# JACart2.net
KiCad netlist of a schematic drawn in EAGLE
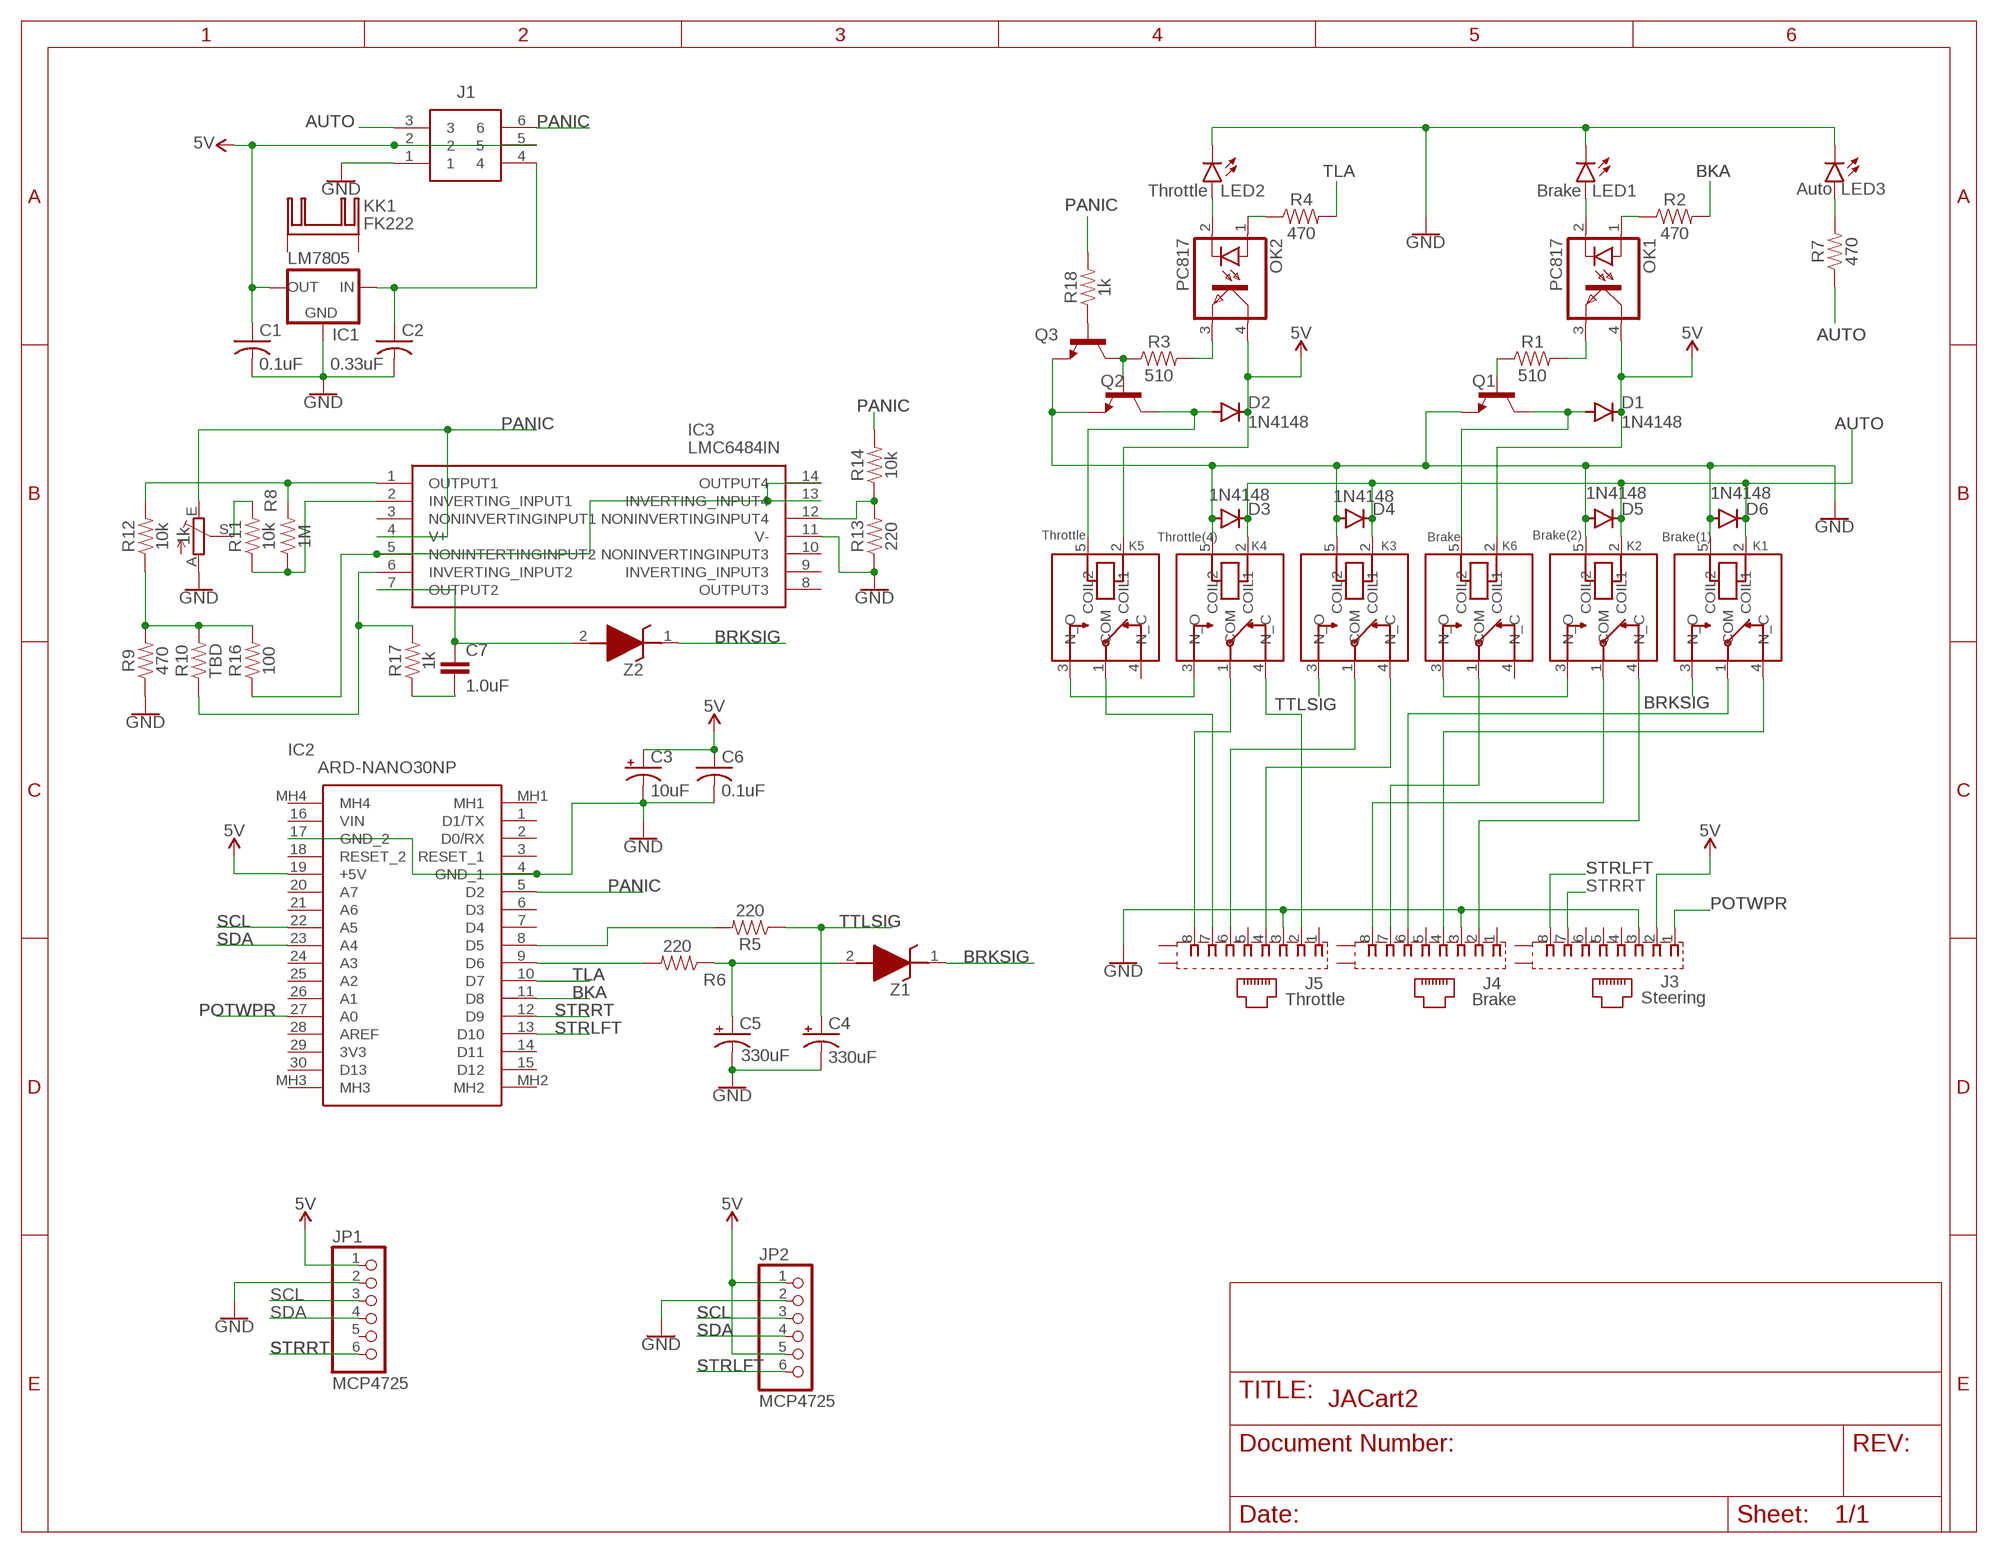
[diagram p0: schematic, sheet 1]

(export (version "E")
  (design (tool "Eeschema 10.0.6"))
  (components
    (comp (ref "C1")
      (value "0.1uF")
      (footprint "eagle-import:C050-024X044")
      (libsource (lib "eagle-import") (part "C-US050-024X044"))
    )
    (comp (ref "C2")
      (value "0.33uF")
      (footprint "eagle-import:C050-024X044")
      (libsource (lib "eagle-import") (part "C-US050-024X044"))
    )
    (comp (ref "C3")
      (value "10uF")
      (footprint "eagle-import:CPOL-RADIAL-2.5MM-5MM")
      (libsource (lib "eagle-import") (part "10UF-POLAR-RADIAL-2.5MM-25V-20%"))
    )
    (comp (ref "C4")
      (value "330uF")
      (footprint "eagle-import:PANASONIC_A")
      (libsource (lib "eagle-import") (part "330UF-PA"))
    )
    (comp (ref "C5")
      (value "330uF")
      (footprint "eagle-import:PANASONIC_A")
      (libsource (lib "eagle-import") (part "330UF-PA"))
    )
    (comp (ref "C6")
      (value "0.1uF")
      (footprint "eagle-import:C050-024X044")
      (fields (field (name "C6") "0.1uF"))
      (libsource (lib "eagle-import") (part "C-US050-024X044"))
    )
    (comp (ref "C7")
      (value "1.0uF")
      (footprint "eagle-import:CAP-PTH-SMALL-KIT")
      (libsource (lib "eagle-import") (part "0.1UF-KIT-EZ-50V-20%"))
    )
    (comp (ref "D1")
      (value "1N4148")
      (footprint "eagle-import:DO35-7")
      (libsource (lib "eagle-import") (part "1N4148DO35-7"))
    )
    (comp (ref "D2")
      (value "1N4148")
      (footprint "eagle-import:DO35-7")
      (libsource (lib "eagle-import") (part "1N4148DO35-7"))
    )
    (comp (ref "D3")
      (value "1N4148")
      (footprint "eagle-import:DO35-7")
      (libsource (lib "eagle-import") (part "1N4148DO35-7"))
    )
    (comp (ref "D4")
      (value "1N4148")
      (footprint "eagle-import:DO35-7")
      (libsource (lib "eagle-import") (part "1N4148DO35-7"))
    )
    (comp (ref "D5")
      (value "1N4148")
      (footprint "eagle-import:DO35-7")
      (libsource (lib "eagle-import") (part "1N4148DO35-7"))
    )
    (comp (ref "D6")
      (value "1N4148")
      (footprint "eagle-import:DO35-7")
      (libsource (lib "eagle-import") (part "1N4148DO35-7"))
    )
    (comp (ref "IC1")
      (value "LM7805")
      (footprint "eagle-import:78XXS")
      (libsource (lib "eagle-import") (part "7805-VR"))
    )
    (comp (ref "IC2")
      (value "ARD-NANO30NP")
      (footprint "eagle-import:ARDNANO30NP")
      (fields (field (name "MOUSER_PART_NUMBER") "992-ARD-NANO30NP"))
      (libsource (lib "eagle-import") (part "ARD-NANO30NP"))
    )
    (comp (ref "IC3")
      (value "LMC6484IN")
      (footprint "eagle-import:DIP794W56P254L1905H533Q14N")
      (fields (field (name "MOUSER_PART_NUMBER") "926-LMC6484IN"))
      (libsource (lib "eagle-import") (part "LMC6484IN"))
    )
    (comp (ref "J1")
      (value "39-30-1060")
      (footprint "eagle-import:39-30-1060_1")
      (fields (field (name "MOUSER_PART_NUMBER") "538-39-30-1060"))
      (libsource (lib "eagle-import") (part "39-30-1060"))
    )
    (comp (ref "J3")
      (value "Steering")
      (footprint "eagle-import:GLX-S-88M")
      (libsource (lib "eagle-import") (part "RJ45-RTANGL"))
    )
    (comp (ref "J4")
      (value "Brake")
      (footprint "eagle-import:GLX-S-88M")
      (fields (field (name "MF") "J4"))
      (libsource (lib "eagle-import") (part "RJ45-RTANGL"))
    )
    (comp (ref "J5")
      (value "Throttle")
      (footprint "eagle-import:GLX-S-88M")
      (libsource (lib "eagle-import") (part "RJ45-RTANGL"))
    )
    (comp (ref "JP1")
      (value "MCP4725")
      (footprint "eagle-import:1X06_ROUND_70")
      (libsource (lib "eagle-import") (part "HEADER-1X670MIL"))
    )
    (comp (ref "JP2")
      (value "MCP4725")
      (footprint "eagle-import:1X06_ROUND_70")
      (libsource (lib "eagle-import") (part "HEADER-1X670MIL"))
    )
    (comp (ref "K1")
      (value "Brake(1)")
      (footprint "eagle-import:RELAY_JS1-5V-F")
      (fields (field (name "MF") "Panasonic Electric") (field (name "MP") "JS1-5V-F"))
      (libsource (lib "eagle-import") (part "RELAY-SPDT"))
    )
    (comp (ref "K2")
      (value "Brake(2)")
      (footprint "eagle-import:RELAY_JS1-5V-F")
      (fields (field (name "MF") "Panasonic Electric") (field (name "MP") "JS1-5V-F"))
      (libsource (lib "eagle-import") (part "RELAY-SPDT"))
    )
    (comp (ref "K3")
      (value "Throttle(3)")
      (footprint "eagle-import:RELAY_JS1-5V-F")
      (fields (field (name "MF") "Panasonic Electric") (field (name "MP") "JS1-5V-F"))
      (libsource (lib "eagle-import") (part "RELAY-SPDT"))
    )
    (comp (ref "K4")
      (value "Throttle(4)")
      (footprint "eagle-import:RELAY_JS1-5V-F")
      (fields (field (name "MF") "Panasonic Electric") (field (name "MP") "JS1-5V-F"))
      (libsource (lib "eagle-import") (part "RELAY-SPDT"))
    )
    (comp (ref "K5")
      (value "Throttle")
      (footprint "eagle-import:RELAY_JS1-5V-F")
      (fields (field (name "MF") "Panasonic Electric") (field (name "MP") "JS1-5V-F"))
      (libsource (lib "eagle-import") (part "RELAY-SPDT"))
    )
    (comp (ref "K6")
      (value "Brake")
      (footprint "eagle-import:RELAY_JS1-5V-F")
      (fields (field (name "MF") "Panasonic Electric") (field (name "MP") "JS1-5V-F"))
      (libsource (lib "eagle-import") (part "RELAY-SPDT"))
    )
    (comp (ref "KK1")
      (value "FK222")
      (footprint "eagle-import:FK222")
      (libsource (lib "eagle-import") (part "FK222"))
    )
    (comp (ref "LED1")
      (value "Brake")
      (footprint "eagle-import:LED_5MM")
      (libsource (lib "eagle-import") (part "LED5MM"))
    )
    (comp (ref "LED2")
      (value "Throttle")
      (footprint "eagle-import:LED_5MM")
      (libsource (lib "eagle-import") (part "LED5MM"))
    )
    (comp (ref "LED3")
      (value "Auto")
      (footprint "eagle-import:LED_5MM")
      (libsource (lib "eagle-import") (part "LED5MM"))
    )
    (comp (ref "OK1")
      (value "PC817")
      (footprint "eagle-import:DIL04")
      (fields (field (name "MPN") "PC817X4J000F"))
      (libsource (lib "eagle-import") (part "PC817"))
    )
    (comp (ref "OK2")
      (value "PC817")
      (footprint "eagle-import:DIL04")
      (fields (field (name "MPN") "PC817X4J000F"))
      (libsource (lib "eagle-import") (part "PC817"))
    )
    (comp (ref "Q1")
      (value "2N3904")
      (footprint "eagle-import:TO92")
      (libsource (lib "eagle-import") (part "2N3904"))
    )
    (comp (ref "Q2")
      (value "2N3904")
      (footprint "eagle-import:TO92")
      (libsource (lib "eagle-import") (part "2N3904"))
    )
    (comp (ref "Q3")
      (value "2N3904")
      (footprint "eagle-import:TO92")
      (libsource (lib "eagle-import") (part "2N3904"))
    )
    (comp (ref "R1")
      (value "510")
      (footprint "eagle-import:AXIAL-0.3")
      (libsource (lib "eagle-import") (part "RESISTORAXIAL-0.3"))
    )
    (comp (ref "R2")
      (value "470")
      (footprint "eagle-import:AXIAL-0.3")
      (libsource (lib "eagle-import") (part "RESISTORAXIAL-0.3"))
    )
    (comp (ref "R3")
      (value "510")
      (footprint "eagle-import:AXIAL-0.3")
      (libsource (lib "eagle-import") (part "RESISTORAXIAL-0.3"))
    )
    (comp (ref "R4")
      (value "470")
      (footprint "eagle-import:AXIAL-0.3")
      (libsource (lib "eagle-import") (part "RESISTORAXIAL-0.3"))
    )
    (comp (ref "R5")
      (value "220")
      (footprint "eagle-import:AXIAL-0.3")
      (libsource (lib "eagle-import") (part "RESISTORAXIAL-0.3"))
    )
    (comp (ref "R6")
      (value "220")
      (footprint "eagle-import:AXIAL-0.3")
      (libsource (lib "eagle-import") (part "RESISTORAXIAL-0.3"))
    )
    (comp (ref "R7")
      (value "470")
      (footprint "eagle-import:AXIAL-0.3")
      (libsource (lib "eagle-import") (part "RESISTORAXIAL-0.3"))
    )
    (comp (ref "R8")
      (value "1M")
      (footprint "eagle-import:AXIAL-0.3")
      (libsource (lib "eagle-import") (part "RESISTORAXIAL-0.3"))
    )
    (comp (ref "R9")
      (value "470")
      (footprint "eagle-import:AXIAL-0.3")
      (libsource (lib "eagle-import") (part "RESISTORAXIAL-0.3"))
    )
    (comp (ref "R10")
      (value "TBD")
      (footprint "eagle-import:AXIAL-0.3")
      (libsource (lib "eagle-import") (part "RESISTORAXIAL-0.3"))
    )
    (comp (ref "R11")
      (value "10k")
      (footprint "eagle-import:AXIAL-0.3")
      (libsource (lib "eagle-import") (part "RESISTORAXIAL-0.3"))
    )
    (comp (ref "R12")
      (value "10k")
      (footprint "eagle-import:AXIAL-0.3")
      (libsource (lib "eagle-import") (part "RESISTORAXIAL-0.3"))
    )
    (comp (ref "R13")
      (value "220")
      (footprint "eagle-import:AXIAL-0.3")
      (libsource (lib "eagle-import") (part "RESISTORAXIAL-0.3"))
    )
    (comp (ref "R14")
      (value "10k")
      (footprint "eagle-import:AXIAL-0.3")
      (libsource (lib "eagle-import") (part "RESISTORAXIAL-0.3"))
    )
    (comp (ref "R15")
      (value "1k")
      (footprint "eagle-import:RJ9W")
      (libsource (lib "eagle-import") (part "TRIM_EU-RJ9W"))
    )
    (comp (ref "R16")
      (value "100")
      (footprint "eagle-import:AXIAL-0.3")
      (libsource (lib "eagle-import") (part "RESISTORAXIAL-0.3"))
    )
    (comp (ref "R17")
      (value "1k")
      (footprint "eagle-import:AXIAL-0.3")
      (libsource (lib "eagle-import") (part "RESISTORAXIAL-0.3"))
    )
    (comp (ref "R18")
      (value "1k")
      (footprint "eagle-import:AXIAL-0.3")
      (libsource (lib "eagle-import") (part "RESISTORAXIAL-0.3"))
    )
    (comp (ref "Z1")
      (value "BAT85S-TR")
      (footprint "eagle-import:DIOAD950W60L350D150")
      (fields (field (name "MOUSER_PART_NUMBER") "78-BAT85S"))
      (libsource (lib "eagle-import") (part "BAT85S-TR"))
    )
    (comp (ref "Z2")
      (value "BAT85S-TR")
      (footprint "eagle-import:DIOAD950W60L350D150")
      (fields (field (name "MOUSER_PART_NUMBER") "78-BAT85S"))
      (libsource (lib "eagle-import") (part "BAT85S-TR"))
    )
  )
  (nets
    (net (code "1") (name "/AUTO") (class "Default")
      (node (ref "D3") (pin "C") (pinfunction "C_C") (pintype "passive"))
      (node (ref "D4") (pin "C") (pinfunction "C_C") (pintype "passive"))
      (node (ref "D5") (pin "C") (pinfunction "C_C") (pintype "passive"))
      (node (ref "D6") (pin "C") (pinfunction "C_C") (pintype "passive"))
      (node (ref "J1") (pin "3") (pinfunction "3_3") (pintype "bidirectional"))
      (node (ref "K1") (pin "2") (pinfunction "COIL1_2") (pintype "passive"))
      (node (ref "K2") (pin "2") (pinfunction "COIL1_2") (pintype "passive"))
      (node (ref "K3") (pin "2") (pinfunction "COIL1_2") (pintype "passive"))
      (node (ref "K4") (pin "2") (pinfunction "COIL1_2") (pintype "passive"))
      (node (ref "R7") (pin "P$1") (pinfunction "1_P$1") (pintype "passive"))
    )
    (net (code "2") (name "/BKA") (class "Default")
      (node (ref "IC2") (pin "11") (pinfunction "D8_11") (pintype "bidirectional"))
      (node (ref "R2") (pin "P$2") (pinfunction "2_P$2") (pintype "passive"))
    )
    (net (code "3") (name "/BRKSIG") (class "Default")
      (node (ref "K1") (pin "3") (pinfunction "N_O_3") (pintype "passive"))
      (node (ref "Z1") (pin "1") (pinfunction "K_1") (pintype "bidirectional"))
      (node (ref "Z2") (pin "1") (pinfunction "K_1") (pintype "bidirectional"))
    )
    (net (code "4") (name "/PANIC") (class "Default")
      (node (ref "IC2") (pin "5") (pinfunction "D2_5") (pintype "bidirectional"))
      (node (ref "IC3") (pin "4") (pinfunction "V+_4") (pintype "bidirectional"))
      (node (ref "J1") (pin "6") (pinfunction "6_6") (pintype "bidirectional"))
      (node (ref "R14") (pin "P$2") (pinfunction "2_P$2") (pintype "passive"))
      (node (ref "R15") (pin "E") (pinfunction "E_E") (pintype "passive"))
      (node (ref "R18") (pin "P$2") (pinfunction "2_P$2") (pintype "passive"))
    )
    (net (code "5") (name "/POTWPR") (class "Default")
      (node (ref "IC2") (pin "27") (pinfunction "A0_27") (pintype "bidirectional"))
      (node (ref "J3") (pin "1") (pinfunction "1_1") (pintype "passive"))
    )
    (net (code "6") (name "/SCL") (class "Default")
      (node (ref "IC2") (pin "22") (pinfunction "A5_22") (pintype "bidirectional"))
      (node (ref "JP1") (pin "3") (pinfunction "3_3") (pintype "passive"))
      (node (ref "JP2") (pin "3") (pinfunction "3_3") (pintype "passive"))
    )
    (net (code "7") (name "/SDA") (class "Default")
      (node (ref "IC2") (pin "23") (pinfunction "A4_23") (pintype "bidirectional"))
      (node (ref "JP1") (pin "4") (pinfunction "4_4") (pintype "passive"))
      (node (ref "JP2") (pin "4") (pinfunction "4_4") (pintype "passive"))
    )
    (net (code "8") (name "/STRLFT") (class "Default")
      (node (ref "IC2") (pin "13") (pinfunction "D10_13") (pintype "bidirectional"))
      (node (ref "J3") (pin "8") (pinfunction "8_8") (pintype "passive"))
      (node (ref "JP2") (pin "6") (pinfunction "6_6") (pintype "passive"))
    )
    (net (code "9") (name "/STRRT") (class "Default")
      (node (ref "IC2") (pin "12") (pinfunction "D9_12") (pintype "bidirectional"))
      (node (ref "J3") (pin "7") (pinfunction "7_7") (pintype "passive"))
      (node (ref "JP1") (pin "6") (pinfunction "6_6") (pintype "passive"))
    )
    (net (code "10") (name "/TLA") (class "Default")
      (node (ref "IC2") (pin "10") (pinfunction "D7_10") (pintype "bidirectional"))
      (node (ref "R4") (pin "P$2") (pinfunction "2_P$2") (pintype "passive"))
    )
    (net (code "11") (name "/TTLSIG") (class "Default")
      (node (ref "C4") (pin "+") (pinfunction "+_+") (pintype "passive"))
      (node (ref "K3") (pin "3") (pinfunction "N_O_3") (pintype "passive"))
      (node (ref "R5") (pin "P$1") (pinfunction "1_P$1") (pintype "passive"))
    )
    (net (code "12") (name "5V") (class "Default")
      (node (ref "C1") (pin "1") (pinfunction "1_1") (pintype "passive"))
      (node (ref "C3") (pin "1") (pinfunction "+_1") (pintype "passive"))
      (node (ref "C6") (pin "1") (pinfunction "1_1") (pintype "passive"))
      (node (ref "D1") (pin "C") (pinfunction "C_C") (pintype "passive"))
      (node (ref "D2") (pin "C") (pinfunction "C_C") (pintype "passive"))
      (node (ref "IC1") (pin "OUT") (pinfunction "OUT_OUT") (pintype "passive"))
      (node (ref "IC2") (pin "19") (pinfunction "+5V_19") (pintype "bidirectional"))
      (node (ref "J1") (pin "2") (pinfunction "2_2") (pintype "bidirectional"))
      (node (ref "J1") (pin "5") (pinfunction "5_5") (pintype "bidirectional"))
      (node (ref "J3") (pin "2") (pinfunction "2_2") (pintype "passive"))
      (node (ref "JP1") (pin "1") (pinfunction "1_1") (pintype "passive"))
      (node (ref "JP2") (pin "1") (pinfunction "1_1") (pintype "passive"))
      (node (ref "JP2") (pin "5") (pinfunction "5_5") (pintype "passive"))
      (node (ref "K5") (pin "2") (pinfunction "COIL1_2") (pintype "passive"))
      (node (ref "K6") (pin "2") (pinfunction "COIL1_2") (pintype "passive"))
      (node (ref "OK1") (pin "4") (pinfunction "COL_4") (pintype "passive"))
      (node (ref "OK2") (pin "4") (pinfunction "COL_4") (pintype "passive"))
    )
    (net (code "13") (name "GND") (class "Default")
      (node (ref "C1") (pin "2") (pinfunction "2_2") (pintype "passive"))
      (node (ref "C2") (pin "2") (pinfunction "2_2") (pintype "passive"))
      (node (ref "C3") (pin "2") (pinfunction "-_2") (pintype "passive"))
      (node (ref "C4") (pin "-") (pinfunction "-_-") (pintype "passive"))
      (node (ref "C5") (pin "-") (pinfunction "-_-") (pintype "passive"))
      (node (ref "C6") (pin "2") (pinfunction "2_2") (pintype "passive"))
      (node (ref "D3") (pin "A") (pinfunction "A_A") (pintype "passive"))
      (node (ref "D4") (pin "A") (pinfunction "A_A") (pintype "passive"))
      (node (ref "D5") (pin "A") (pinfunction "A_A") (pintype "passive"))
      (node (ref "D6") (pin "A") (pinfunction "A_A") (pintype "passive"))
      (node (ref "IC1") (pin "GND") (pinfunction "GND_GND") (pintype "input"))
      (node (ref "IC2") (pin "17") (pinfunction "GND_2_17") (pintype "bidirectional"))
      (node (ref "IC2") (pin "4") (pinfunction "GND_1_4") (pintype "bidirectional"))
      (node (ref "IC3") (pin "11") (pinfunction "V-_11") (pintype "bidirectional"))
      (node (ref "J1") (pin "1") (pinfunction "1_1") (pintype "bidirectional"))
      (node (ref "J3") (pin "3") (pinfunction "3_3") (pintype "passive"))
      (node (ref "J4") (pin "3") (pinfunction "3_3") (pintype "passive"))
      (node (ref "J5") (pin "3") (pinfunction "3_3") (pintype "passive"))
      (node (ref "JP1") (pin "2") (pinfunction "2_2") (pintype "passive"))
      (node (ref "JP2") (pin "2") (pinfunction "2_2") (pintype "passive"))
      (node (ref "K1") (pin "5") (pinfunction "COIL2_5") (pintype "passive"))
      (node (ref "K2") (pin "5") (pinfunction "COIL2_5") (pintype "passive"))
      (node (ref "K3") (pin "5") (pinfunction "COIL2_5") (pintype "passive"))
      (node (ref "K4") (pin "5") (pinfunction "COIL2_5") (pintype "passive"))
      (node (ref "LED1") (pin "K") (pinfunction "C_K") (pintype "passive"))
      (node (ref "LED2") (pin "K") (pinfunction "C_K") (pintype "passive"))
      (node (ref "LED3") (pin "K") (pinfunction "C_K") (pintype "passive"))
      (node (ref "Q1") (pin "3") (pinfunction "E_3") (pintype "passive"))
      (node (ref "Q2") (pin "3") (pinfunction "E_3") (pintype "passive"))
      (node (ref "Q3") (pin "3") (pinfunction "E_3") (pintype "passive"))
      (node (ref "R13") (pin "P$1") (pinfunction "1_P$1") (pintype "passive"))
      (node (ref "R15") (pin "A") (pinfunction "A_A") (pintype "passive"))
      (node (ref "R9") (pin "P$1") (pinfunction "1_P$1") (pintype "passive"))
    )
    (net (code "14") (name "Net-(C2-Pad1)") (class "Default")
      (node (ref "C2") (pin "1") (pinfunction "1_1") (pintype "passive"))
      (node (ref "IC1") (pin "IN") (pinfunction "IN_IN") (pintype "input"))
      (node (ref "J1") (pin "4") (pinfunction "4_4") (pintype "bidirectional"))
    )
    (net (code "15") (name "Net-(IC2-D5)") (class "Default")
      (node (ref "IC2") (pin "8") (pinfunction "D5_8") (pintype "bidirectional"))
      (node (ref "R5") (pin "P$2") (pinfunction "2_P$2") (pintype "passive"))
    )
    (net (code "16") (name "Net-(IC2-D6)") (class "Default")
      (node (ref "IC2") (pin "9") (pinfunction "D6_9") (pintype "bidirectional"))
      (node (ref "R6") (pin "P$2") (pinfunction "2_P$2") (pintype "passive"))
    )
    (net (code "17") (name "Net-(IC3-INVERTING_INPUT1)") (class "Default")
      (node (ref "IC3") (pin "2") (pinfunction "INVERTING_INPUT1_2") (pintype "bidirectional"))
      (node (ref "R11") (pin "P$1") (pinfunction "1_P$1") (pintype "passive"))
      (node (ref "R8") (pin "P$1") (pinfunction "1_P$1") (pintype "passive"))
    )
    (net (code "18") (name "Net-(IC3-INVERTING_INPUT2)") (class "Default")
      (node (ref "IC3") (pin "6") (pinfunction "INVERTING_INPUT2_6") (pintype "bidirectional"))
      (node (ref "R10") (pin "P$1") (pinfunction "1_P$1") (pintype "passive"))
      (node (ref "R17") (pin "P$2") (pinfunction "2_P$2") (pintype "passive"))
    )
    (net (code "19") (name "Net-(IC3-INVERTING_INPUT4)") (class "Default")
      (node (ref "IC3") (pin "13") (pinfunction "INVERTING_INPUT4_13") (pintype "bidirectional"))
      (node (ref "IC3") (pin "14") (pinfunction "OUTPUT4_14") (pintype "bidirectional"))
      (node (ref "IC3") (pin "5") (pinfunction "NONINTERTINGINPUT2_5") (pintype "bidirectional"))
      (node (ref "R16") (pin "P$1") (pinfunction "1_P$1") (pintype "passive"))
    )
    (net (code "20") (name "Net-(IC3-NONINVERTINGINPUT4)") (class "Default")
      (node (ref "IC3") (pin "12") (pinfunction "NONINVERTINGINPUT4_12") (pintype "bidirectional"))
      (node (ref "R13") (pin "P$2") (pinfunction "2_P$2") (pintype "passive"))
      (node (ref "R14") (pin "P$1") (pinfunction "1_P$1") (pintype "passive"))
    )
    (net (code "21") (name "Net-(IC3-OUTPUT1)") (class "Default")
      (node (ref "IC3") (pin "1") (pinfunction "OUTPUT1_1") (pintype "bidirectional"))
      (node (ref "R12") (pin "P$2") (pinfunction "2_P$2") (pintype "passive"))
      (node (ref "R8") (pin "P$2") (pinfunction "2_P$2") (pintype "passive"))
    )
    (net (code "22") (name "Net-(IC3-OUTPUT2)") (class "Default")
      (node (ref "C7") (pin "1") (pinfunction "1_1") (pintype "passive"))
      (node (ref "IC3") (pin "7") (pinfunction "OUTPUT2_7") (pintype "bidirectional"))
      (node (ref "Z2") (pin "2") (pinfunction "A_2") (pintype "bidirectional"))
    )
    (net (code "23") (name "Net-(K1-COM)") (class "Default")
      (node (ref "J4") (pin "6") (pinfunction "6_6") (pintype "passive"))
      (node (ref "K1") (pin "1") (pinfunction "COM_1") (pintype "passive"))
    )
    (net (code "24") (name "Net-(K1-N_C)") (class "Default")
      (node (ref "J4") (pin "4") (pinfunction "4_4") (pintype "passive"))
      (node (ref "K1") (pin "4") (pinfunction "N_C_4") (pintype "passive"))
    )
    (net (code "25") (name "Net-(K2-COM)") (class "Default")
      (node (ref "J4") (pin "8") (pinfunction "8_8") (pintype "passive"))
      (node (ref "K2") (pin "1") (pinfunction "COM_1") (pintype "passive"))
    )
    (net (code "26") (name "Net-(K2-N_C)") (class "Default")
      (node (ref "J4") (pin "2") (pinfunction "2_2") (pintype "passive"))
      (node (ref "K2") (pin "4") (pinfunction "N_C_4") (pintype "passive"))
    )
    (net (code "27") (name "Net-(K2-N_O)") (class "Default")
      (node (ref "K2") (pin "3") (pinfunction "N_O_3") (pintype "passive"))
      (node (ref "K6") (pin "3") (pinfunction "N_O_3") (pintype "passive"))
    )
    (net (code "28") (name "Net-(K3-COM)") (class "Default")
      (node (ref "J5") (pin "6") (pinfunction "6_6") (pintype "passive"))
      (node (ref "K3") (pin "1") (pinfunction "COM_1") (pintype "passive"))
    )
    (net (code "29") (name "Net-(K3-N_C)") (class "Default")
      (node (ref "J5") (pin "4") (pinfunction "4_4") (pintype "passive"))
      (node (ref "K3") (pin "4") (pinfunction "N_C_4") (pintype "passive"))
    )
    (net (code "30") (name "Net-(K4-COM)") (class "Default")
      (node (ref "J5") (pin "8") (pinfunction "8_8") (pintype "passive"))
      (node (ref "K4") (pin "1") (pinfunction "COM_1") (pintype "passive"))
    )
    (net (code "31") (name "Net-(K4-N_C)") (class "Default")
      (node (ref "J5") (pin "2") (pinfunction "2_2") (pintype "passive"))
      (node (ref "K4") (pin "4") (pinfunction "N_C_4") (pintype "passive"))
    )
    (net (code "32") (name "Net-(K4-N_O)") (class "Default")
      (node (ref "K4") (pin "3") (pinfunction "N_O_3") (pintype "passive"))
      (node (ref "K5") (pin "3") (pinfunction "N_O_3") (pintype "passive"))
    )
    (net (code "33") (name "Net-(K5-COIL2)") (class "Default")
      (node (ref "D2") (pin "A") (pinfunction "A_A") (pintype "passive"))
      (node (ref "K5") (pin "5") (pinfunction "COIL2_5") (pintype "passive"))
      (node (ref "Q2") (pin "1") (pinfunction "C_1") (pintype "passive"))
    )
    (net (code "34") (name "Net-(K5-COM)") (class "Default")
      (node (ref "J5") (pin "7") (pinfunction "7_7") (pintype "passive"))
      (node (ref "K5") (pin "1") (pinfunction "COM_1") (pintype "passive"))
    )
    (net (code "35") (name "Net-(K6-COIL2)") (class "Default")
      (node (ref "D1") (pin "A") (pinfunction "A_A") (pintype "passive"))
      (node (ref "K6") (pin "5") (pinfunction "COIL2_5") (pintype "passive"))
      (node (ref "Q1") (pin "1") (pinfunction "C_1") (pintype "passive"))
    )
    (net (code "36") (name "Net-(K6-COM)") (class "Default")
      (node (ref "J4") (pin "7") (pinfunction "7_7") (pintype "passive"))
      (node (ref "K6") (pin "1") (pinfunction "COM_1") (pintype "passive"))
    )
    (net (code "37") (name "Net-(OK1-A)") (class "Default")
      (node (ref "OK1") (pin "1") (pinfunction "A_1") (pintype "passive"))
      (node (ref "R2") (pin "P$1") (pinfunction "1_P$1") (pintype "passive"))
    )
    (net (code "38") (name "Net-(OK1-C)") (class "Default")
      (node (ref "LED1") (pin "A") (pinfunction "A_A") (pintype "passive"))
      (node (ref "OK1") (pin "2") (pinfunction "C_2") (pintype "passive"))
    )
    (net (code "39") (name "Net-(OK1-EMIT)") (class "Default")
      (node (ref "OK1") (pin "3") (pinfunction "EMIT_3") (pintype "passive"))
      (node (ref "R1") (pin "P$2") (pinfunction "2_P$2") (pintype "passive"))
    )
    (net (code "40") (name "Net-(OK2-A)") (class "Default")
      (node (ref "OK2") (pin "1") (pinfunction "A_1") (pintype "passive"))
      (node (ref "R4") (pin "P$1") (pinfunction "1_P$1") (pintype "passive"))
    )
    (net (code "41") (name "Net-(OK2-C)") (class "Default")
      (node (ref "LED2") (pin "A") (pinfunction "A_A") (pintype "passive"))
      (node (ref "OK2") (pin "2") (pinfunction "C_2") (pintype "passive"))
    )
    (net (code "42") (name "Net-(OK2-EMIT)") (class "Default")
      (node (ref "OK2") (pin "3") (pinfunction "EMIT_3") (pintype "passive"))
      (node (ref "R3") (pin "P$2") (pinfunction "2_P$2") (pintype "passive"))
    )
    (net (code "43") (name "Net-(Q1-B)") (class "Default")
      (node (ref "Q1") (pin "2") (pinfunction "B_2") (pintype "passive"))
      (node (ref "R1") (pin "P$1") (pinfunction "1_P$1") (pintype "passive"))
    )
    (net (code "44") (name "Net-(Q2-B)") (class "Default")
      (node (ref "Q2") (pin "2") (pinfunction "B_2") (pintype "passive"))
      (node (ref "Q3") (pin "1") (pinfunction "C_1") (pintype "passive"))
      (node (ref "R3") (pin "P$1") (pinfunction "1_P$1") (pintype "passive"))
    )
    (net (code "45") (name "Net-(Q3-B)") (class "Default")
      (node (ref "Q3") (pin "2") (pinfunction "B_2") (pintype "passive"))
      (node (ref "R18") (pin "P$1") (pinfunction "1_P$1") (pintype "passive"))
    )
    (net (code "46") (name "Net-(R6-1)") (class "Default")
      (node (ref "C5") (pin "+") (pinfunction "+_+") (pintype "passive"))
      (node (ref "R6") (pin "P$1") (pinfunction "1_P$1") (pintype "passive"))
      (node (ref "Z1") (pin "2") (pinfunction "A_2") (pintype "bidirectional"))
    )
    (net (code "47") (name "Net-(R7-2)") (class "Default")
      (node (ref "LED3") (pin "A") (pinfunction "A_A") (pintype "passive"))
      (node (ref "R7") (pin "P$2") (pinfunction "2_P$2") (pintype "passive"))
    )
    (net (code "48") (name "Net-(R10-2)") (class "Default")
      (node (ref "R10") (pin "P$2") (pinfunction "2_P$2") (pintype "passive"))
      (node (ref "R12") (pin "P$1") (pinfunction "1_P$1") (pintype "passive"))
      (node (ref "R16") (pin "P$2") (pinfunction "2_P$2") (pintype "passive"))
      (node (ref "R9") (pin "P$2") (pinfunction "2_P$2") (pintype "passive"))
    )
    (net (code "49") (name "Net-(R11-2)") (class "Default")
      (node (ref "R11") (pin "P$2") (pinfunction "2_P$2") (pintype "passive"))
      (node (ref "R15") (pin "S") (pinfunction "S_S") (pintype "passive"))
    )
    (net (code "50") (name "Net-(R17-1)") (class "Default")
      (node (ref "C7") (pin "2") (pinfunction "2_2") (pintype "passive"))
      (node (ref "R17") (pin "P$1") (pinfunction "1_P$1") (pintype "passive"))
    )
    (net (code "51") (name "unconnected-(IC2-3V3-Pad29)") (class "Default")
      (node (ref "IC2") (pin "29") (pinfunction "3V3_29") (pintype "bidirectional"))
    )
    (net (code "52") (name "unconnected-(IC2-A1-Pad26)") (class "Default")
      (node (ref "IC2") (pin "26") (pinfunction "A1_26") (pintype "bidirectional"))
    )
    (net (code "53") (name "unconnected-(IC2-A2-Pad25)") (class "Default")
      (node (ref "IC2") (pin "25") (pinfunction "A2_25") (pintype "bidirectional"))
    )
    (net (code "54") (name "unconnected-(IC2-A3-Pad24)") (class "Default")
      (node (ref "IC2") (pin "24") (pinfunction "A3_24") (pintype "bidirectional"))
    )
    (net (code "55") (name "unconnected-(IC2-A6-Pad21)") (class "Default")
      (node (ref "IC2") (pin "21") (pinfunction "A6_21") (pintype "bidirectional"))
    )
    (net (code "56") (name "unconnected-(IC2-A7-Pad20)") (class "Default")
      (node (ref "IC2") (pin "20") (pinfunction "A7_20") (pintype "bidirectional"))
    )
    (net (code "57") (name "unconnected-(IC2-AREF-Pad28)") (class "Default")
      (node (ref "IC2") (pin "28") (pinfunction "AREF_28") (pintype "bidirectional"))
    )
    (net (code "58") (name "unconnected-(IC2-D0{slash}RX-Pad2)") (class "Default")
      (node (ref "IC2") (pin "2") (pinfunction "D0/RX_2") (pintype "bidirectional"))
    )
    (net (code "59") (name "unconnected-(IC2-D1{slash}TX-Pad1)") (class "Default")
      (node (ref "IC2") (pin "1") (pinfunction "D1/TX_1") (pintype "bidirectional"))
    )
    (net (code "60") (name "unconnected-(IC2-D3-Pad6)") (class "Default")
      (node (ref "IC2") (pin "6") (pinfunction "D3_6") (pintype "bidirectional"))
    )
    (net (code "61") (name "unconnected-(IC2-D4-Pad7)") (class "Default")
      (node (ref "IC2") (pin "7") (pinfunction "D4_7") (pintype "bidirectional"))
    )
    (net (code "62") (name "unconnected-(IC2-D11-Pad14)") (class "Default")
      (node (ref "IC2") (pin "14") (pinfunction "D11_14") (pintype "bidirectional"))
    )
    (net (code "63") (name "unconnected-(IC2-D12-Pad15)") (class "Default")
      (node (ref "IC2") (pin "15") (pinfunction "D12_15") (pintype "bidirectional"))
    )
    (net (code "64") (name "unconnected-(IC2-D13-Pad30)") (class "Default")
      (node (ref "IC2") (pin "30") (pinfunction "D13_30") (pintype "bidirectional"))
    )
    (net (code "65") (name "unconnected-(IC2-PadMH1)") (class "Default")
      (node (ref "IC2") (pin "MH1") (pinfunction "MH1_MH1") (pintype "bidirectional"))
    )
    (net (code "66") (name "unconnected-(IC2-PadMH2)") (class "Default")
      (node (ref "IC2") (pin "MH2") (pinfunction "MH2_MH2") (pintype "bidirectional"))
    )
    (net (code "67") (name "unconnected-(IC2-PadMH3)") (class "Default")
      (node (ref "IC2") (pin "MH3") (pinfunction "MH3_MH3") (pintype "bidirectional"))
    )
    (net (code "68") (name "unconnected-(IC2-PadMH4)") (class "Default")
      (node (ref "IC2") (pin "MH4") (pinfunction "MH4_MH4") (pintype "bidirectional"))
    )
    (net (code "69") (name "unconnected-(IC2-RESET_1-Pad3)") (class "Default")
      (node (ref "IC2") (pin "3") (pinfunction "RESET_1_3") (pintype "bidirectional"))
    )
    (net (code "70") (name "unconnected-(IC2-RESET_2-Pad18)") (class "Default")
      (node (ref "IC2") (pin "18") (pinfunction "RESET_2_18") (pintype "bidirectional"))
    )
    (net (code "71") (name "unconnected-(IC2-VIN-Pad16)") (class "Default")
      (node (ref "IC2") (pin "16") (pinfunction "VIN_16") (pintype "bidirectional"))
    )
    (net (code "72") (name "unconnected-(IC3-INVERTING_INPUT3-Pad9)") (class "Default")
      (node (ref "IC3") (pin "9") (pinfunction "INVERTING_INPUT3_9") (pintype "bidirectional"))
    )
    (net (code "73") (name "unconnected-(IC3-NONINVERTINGINPUT1-Pad3)") (class "Default")
      (node (ref "IC3") (pin "3") (pinfunction "NONINVERTINGINPUT1_3") (pintype "bidirectional"))
    )
    (net (code "74") (name "unconnected-(IC3-NONINVERTINGINPUT3-Pad10)") (class "Default")
      (node (ref "IC3") (pin "10") (pinfunction "NONINVERTINGINPUT3_10") (pintype "bidirectional"))
    )
    (net (code "75") (name "unconnected-(IC3-OUTPUT3-Pad8)") (class "Default")
      (node (ref "IC3") (pin "8") (pinfunction "OUTPUT3_8") (pintype "bidirectional"))
    )
    (net (code "76") (name "unconnected-(J3-Pad4)") (class "Default")
      (node (ref "J3") (pin "4") (pinfunction "4_4") (pintype "passive"))
    )
    (net (code "77") (name "unconnected-(J3-Pad5)") (class "Default")
      (node (ref "J3") (pin "5") (pinfunction "5_5") (pintype "passive"))
    )
    (net (code "78") (name "unconnected-(J3-Pad6)") (class "Default")
      (node (ref "J3") (pin "6") (pinfunction "6_6") (pintype "passive"))
    )
    (net (code "79") (name "unconnected-(J3-PadS1)") (class "Default")
      (node (ref "J3") (pin "S1") (pinfunction "S1_S1") (pintype "passive"))
    )
    (net (code "80") (name "unconnected-(J3-PadS2)") (class "Default")
      (node (ref "J3") (pin "S2") (pinfunction "S2_S2") (pintype "passive"))
    )
    (net (code "81") (name "unconnected-(J4-Pad1)") (class "Default")
      (node (ref "J4") (pin "1") (pinfunction "1_1") (pintype "passive"))
    )
    (net (code "82") (name "unconnected-(J4-Pad5)") (class "Default")
      (node (ref "J4") (pin "5") (pinfunction "5_5") (pintype "passive"))
    )
    (net (code "83") (name "unconnected-(J4-PadS1)") (class "Default")
      (node (ref "J4") (pin "S1") (pinfunction "S1_S1") (pintype "passive"))
    )
    (net (code "84") (name "unconnected-(J4-PadS2)") (class "Default")
      (node (ref "J4") (pin "S2") (pinfunction "S2_S2") (pintype "passive"))
    )
    (net (code "85") (name "unconnected-(J5-Pad1)") (class "Default")
      (node (ref "J5") (pin "1") (pinfunction "1_1") (pintype "passive"))
    )
    (net (code "86") (name "unconnected-(J5-Pad5)") (class "Default")
      (node (ref "J5") (pin "5") (pinfunction "5_5") (pintype "passive"))
    )
    (net (code "87") (name "unconnected-(J5-PadS1)") (class "Default")
      (node (ref "J5") (pin "S1") (pinfunction "S1_S1") (pintype "passive"))
    )
    (net (code "88") (name "unconnected-(J5-PadS2)") (class "Default")
      (node (ref "J5") (pin "S2") (pinfunction "S2_S2") (pintype "passive"))
    )
    (net (code "89") (name "unconnected-(JP1-Pad5)") (class "Default")
      (node (ref "JP1") (pin "5") (pinfunction "5_5") (pintype "passive"))
    )
    (net (code "90") (name "unconnected-(K5-N_C-Pad4)") (class "Default")
      (node (ref "K5") (pin "4") (pinfunction "N_C_4") (pintype "passive"))
    )
    (net (code "91") (name "unconnected-(K6-N_C-Pad4)") (class "Default")
      (node (ref "K6") (pin "4") (pinfunction "N_C_4") (pintype "passive"))
    )
    (net (code "92") (name "unconnected-(KK1-K-PadA2,8)") (class "Default")
      (node (ref "KK1") (pin "A2,8") (pinfunction "K_A2,8") (pintype "passive"))
    )
    (net (code "93") (name "unconnected-(KK1-K-PadB2,8)") (class "Default")
      (node (ref "KK1") (pin "B2,8") (pinfunction "K_B2,8") (pintype "passive"))
    )
  )
)
